# hall_sensor_v2.net
KiCad netlist of a schematic drawn in EAGLE
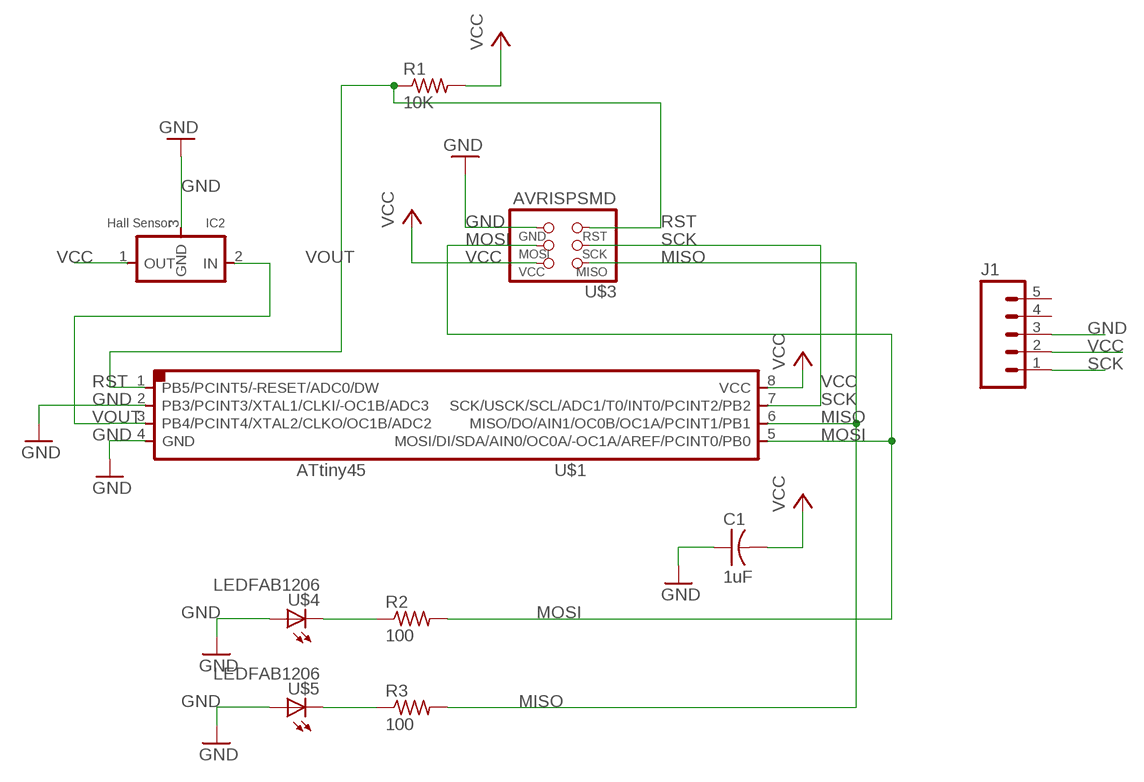
[diagram p0: schematic, sheet 1]

(export (version "E")
  (design (tool "Eeschema 10.0.6"))
  (components
    (comp (ref "C1")
      (value "1uF")
      (footprint "eagle-import:C1206FAB")
      (libsource (lib "eagle-import") (part "CAP-US1206FAB"))
    )
    (comp (ref "IC2")
      (value "Hall Sensor")
      (footprint "eagle-import:SOT23")
      (libsource (lib "eagle-import") (part "REGULATORSOT23"))
    )
    (comp (ref "J1")
      (value "M05LOCK")
      (footprint "eagle-import:1X05_LOCK")
      (libsource (lib "eagle-import") (part "M05LOCK"))
    )
    (comp (ref "R1")
      (value "10K")
      (footprint "eagle-import:R1206FAB")
      (libsource (lib "eagle-import") (part "RES-US1206FAB"))
    )
    (comp (ref "R2")
      (value "100")
      (footprint "eagle-import:R1206FAB")
      (libsource (lib "eagle-import") (part "RES-US1206FAB"))
    )
    (comp (ref "R3")
      (value "100")
      (footprint "eagle-import:R1206FAB")
      (libsource (lib "eagle-import") (part "RES-US1206FAB"))
    )
    (comp (ref "U$1")
      (value "ATTINY45SI")
      (footprint "eagle-import:SOIC8")
      (libsource (lib "eagle-import") (part "ATTINY45SI"))
    )
    (comp (ref "U$3")
      (value "AVRISPSMD")
      (footprint "eagle-import:2X03SMD")
      (libsource (lib "eagle-import") (part "AVRISPSMD"))
    )
    (comp (ref "U$4")
      (value "LEDFAB1206")
      (footprint "eagle-import:LED1206FAB")
      (libsource (lib "eagle-import") (part "LEDFAB1206"))
    )
    (comp (ref "U$5")
      (value "LEDFAB1206")
      (footprint "eagle-import:LED1206FAB")
      (libsource (lib "eagle-import") (part "LEDFAB1206"))
    )
  )
  (nets
    (net (code "1") (name "/MISO") (class "Default")
      (node (ref "R3") (pin "2") (pinfunction "2_2") (pintype "passive"))
      (node (ref "U$1") (pin "6") (pinfunction "MISO/DO/AIN1/OC0B/OC1A/PCINT1/PB1_6") (pintype "bidirectional"))
      (node (ref "U$3") (pin "1") (pinfunction "MISO_1") (pintype "passive"))
    )
    (net (code "2") (name "/MOSI") (class "Default")
      (node (ref "R2") (pin "2") (pinfunction "2_2") (pintype "passive"))
      (node (ref "U$1") (pin "5") (pinfunction "MOSI/DI/SDA/AIN0/OC0A/-OC1A/AREF/PCINT0/PB0_5") (pintype "bidirectional"))
      (node (ref "U$3") (pin "4") (pinfunction "MOSI_4") (pintype "passive"))
    )
    (net (code "3") (name "/RST") (class "Default")
      (node (ref "R1") (pin "1") (pinfunction "1_1") (pintype "passive"))
      (node (ref "U$1") (pin "1") (pinfunction "PB5/PCINT5/-RESET/ADC0/DW_1") (pintype "bidirectional"))
      (node (ref "U$3") (pin "5") (pinfunction "RST_5") (pintype "passive"))
    )
    (net (code "4") (name "/SCK") (class "Default")
      (node (ref "J1") (pin "1") (pinfunction "1_1") (pintype "passive"))
      (node (ref "U$1") (pin "7") (pinfunction "SCK/USCK/SCL/ADC1/T0/INT0/PCINT2/PB2_7") (pintype "bidirectional"))
      (node (ref "U$3") (pin "3") (pinfunction "SCK_3") (pintype "passive"))
    )
    (net (code "5") (name "/VOUT") (class "Default")
      (node (ref "IC2") (pin "2") (pinfunction "IN_2") (pintype "bidirectional"))
      (node (ref "U$1") (pin "3") (pinfunction "PB4/PCINT4/XTAL2/CLKO/OC1B/ADC2_3") (pintype "bidirectional"))
    )
    (net (code "6") (name "GND") (class "Default")
      (node (ref "C1") (pin "1") (pinfunction "1_1") (pintype "passive"))
      (node (ref "IC2") (pin "3") (pinfunction "GND_3") (pintype "bidirectional"))
      (node (ref "J1") (pin "3") (pinfunction "3_3") (pintype "passive"))
      (node (ref "U$1") (pin "2") (pinfunction "PB3/PCINT3/XTAL1/CLKI/-OC1B/ADC3_2") (pintype "bidirectional"))
      (node (ref "U$1") (pin "4") (pinfunction "GND_4") (pintype "bidirectional"))
      (node (ref "U$3") (pin "6") (pinfunction "GND_6") (pintype "passive"))
      (node (ref "U$4") (pin "1") (pinfunction "A_1") (pintype "passive"))
      (node (ref "U$5") (pin "1") (pinfunction "A_1") (pintype "passive"))
    )
    (net (code "7") (name "Net-(U$4-C)") (class "Default")
      (node (ref "R2") (pin "1") (pinfunction "1_1") (pintype "passive"))
      (node (ref "U$4") (pin "2") (pinfunction "C_2") (pintype "passive"))
    )
    (net (code "8") (name "Net-(U$5-C)") (class "Default")
      (node (ref "R3") (pin "1") (pinfunction "1_1") (pintype "passive"))
      (node (ref "U$5") (pin "2") (pinfunction "C_2") (pintype "passive"))
    )
    (net (code "9") (name "VCC") (class "Default")
      (node (ref "C1") (pin "2") (pinfunction "2_2") (pintype "passive"))
      (node (ref "IC2") (pin "1") (pinfunction "OUT_1") (pintype "bidirectional"))
      (node (ref "J1") (pin "2") (pinfunction "2_2") (pintype "passive"))
      (node (ref "R1") (pin "2") (pinfunction "2_2") (pintype "passive"))
      (node (ref "U$1") (pin "8") (pinfunction "VCC_8") (pintype "bidirectional"))
      (node (ref "U$3") (pin "2") (pinfunction "VCC_2") (pintype "passive"))
    )
    (net (code "10") (name "unconnected-(J1-Pad4)") (class "Default")
      (node (ref "J1") (pin "4") (pinfunction "4_4") (pintype "passive"))
    )
    (net (code "11") (name "unconnected-(J1-Pad5)") (class "Default")
      (node (ref "J1") (pin "5") (pinfunction "5_5") (pintype "passive"))
    )
  )
)
